# GPS.net
KiCad netlist of a schematic drawn in Altium Designer
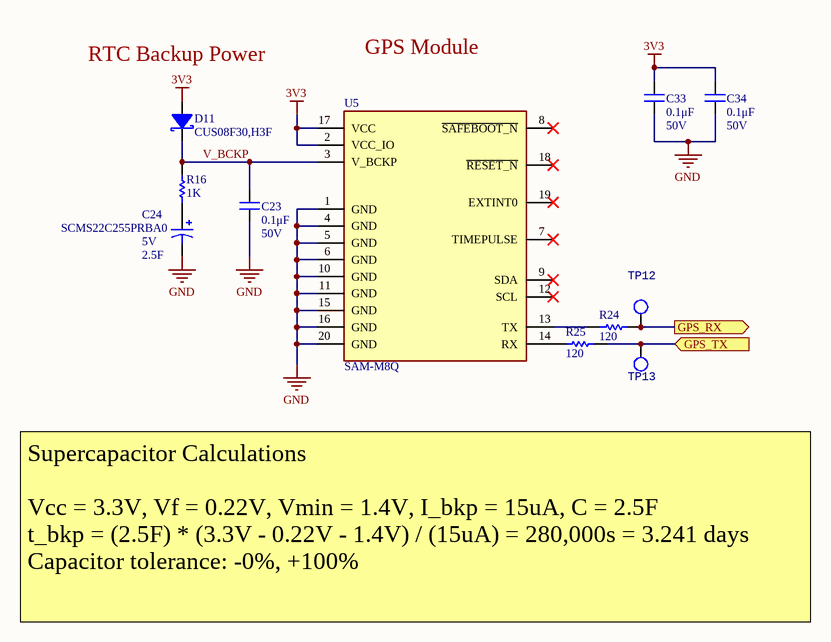
[diagram p0: GPS.SchDoc]

(export (version "E")
  (design (tool "Eeschema 10.0.6"))
  (components
    (comp (ref "C23")
      (value "0.1μF")
      (footprint "CAP2012")
      (description "CAP CER 0.1UF 50V X7R 0805")
      (fields
        (field (name "TOLERANCE") "10%")
        (field (name "VOLTAGE RATING") "50V")
        (field (name "Comment") "CAP_0.1uF_50V_0805")
      )
      (libsource (lib "UWRT_Schematic_Library_2020") (part "CAP_0.1uF_50V_0805"))
    )
    (comp (ref "C24")
      (value "CAP_2.5F_5V")
      (footprint "UWRT_Footprint_Library_2020:SCMS22C255PRBA0")
      (description "CAP 2.5F 5V")
      (fields
        (field (name "MANUFACTURER PART NUMBER 1") "SCMS22C255PRBA0")
        (field (name "TOLERANCE") "0%, +100%")
        (field (name "VOLTAGE RATING") "5V")
        (field (name "CAPACITANCE") "2.5F")
      )
      (libsource (lib "UWRT_Schematic_Library_2020") (part "CAP_2.5F_5V"))
    )
    (comp (ref "C33")
      (value "0.1μF")
      (footprint "CAP2012")
      (description "CAP CER 0.1UF 50V X7R 0805")
      (fields
        (field (name "TOLERANCE") "10%")
        (field (name "VOLTAGE RATING") "50V")
        (field (name "Comment") "CAP_0.1uF_50V_0805")
      )
      (libsource (lib "UWRT_Schematic_Library_2020") (part "CAP_0.1uF_50V_0805"))
    )
    (comp (ref "C34")
      (value "0.1μF")
      (footprint "CAP2012")
      (description "CAP CER 0.1UF 50V X7R 0805")
      (fields
        (field (name "TOLERANCE") "10%")
        (field (name "VOLTAGE RATING") "50V")
        (field (name "Comment") "CAP_0.1uF_50V_0805")
      )
      (libsource (lib "UWRT_Schematic_Library_2020") (part "CAP_0.1uF_50V_0805"))
    )
    (comp (ref "D11")
      (value "DIO_SCHOTTKY_30V_800mA")
      (footprint "SOD-323_UNIDIR")
      (description "DIODE SCHOTTKY 30V 800MA USC")
      (fields (field (name "MANUFACTURER PART NUMBER 1") "CUS08F30,H3F"))
      (libsource (lib "UWRT_Schematic_Library_2020") (part "DIO_SCHOTTKY_30V_800mA"))
    )
    (comp (ref "R16")
      (value "1K")
      (footprint "RESC0603(1608)_N")
      (description "RES SMD 1K OHM 5% 1/10W 0603")
      (fields (field (name "TOLERANCE") "5%") (field (name "Comment") "RES_1K_0603"))
      (libsource (lib "UWRT_Schematic_Library_2020") (part "RES_1K_0603"))
    )
    (comp (ref "R24")
      (value "120")
      (footprint "RESC0603(1608)_N")
      (description "RES SMD 120 OHM 5% 1/10W 0603")
      (fields (field (name "TOLERANCE") "5%") (field (name "Comment") "RES_120R_0603"))
      (libsource (lib "UWRT_Schematic_Library_2020") (part "RES_120R_0603"))
    )
    (comp (ref "R25")
      (value "120")
      (footprint "RESC0603(1608)_N")
      (description "RES SMD 120 OHM 5% 1/10W 0603")
      (fields (field (name "TOLERANCE") "5%") (field (name "Comment") "RES_120R_0603"))
      (libsource (lib "UWRT_Schematic_Library_2020") (part "RES_120R_0603"))
    )
    (comp (ref "TP12")
      (value "TESTPOINT_LOOP")
      (footprint "TESTPOINT_LOOP")
      (description "PC TEST POINT MINIATURE WHITE")
      (libsource (lib "UWRT_Schematic_Library_2020") (part "TESTPOINT_LOOP"))
    )
    (comp (ref "TP13")
      (value "TESTPOINT_LOOP")
      (footprint "TESTPOINT_LOOP")
      (description "PC TEST POINT MINIATURE WHITE")
      (libsource (lib "UWRT_Schematic_Library_2020") (part "TESTPOINT_LOOP"))
    )
    (comp (ref "U5")
      (value "SAM-M8Q")
      (footprint "SAM-M8Q")
      (description "Rf Rx Galileo 1.575GHZ/1.602GHZ")
      (libsource (lib "UWRT_Schematic_Library_2020") (part "SAM-M8Q"))
    )
  )
  (nets
    (net (code "1") (name "/GPS_RX") (class "Default")
      (node (ref "R24") (pin "2") (pinfunction "2_2") (pintype "passive"))
      (node (ref "TP12") (pin "1") (pintype "passive"))
    )
    (net (code "2") (name "/GPS_TX") (class "Default")
      (node (ref "R25") (pin "2") (pinfunction "2_2") (pintype "passive"))
      (node (ref "TP13") (pin "1") (pintype "passive"))
    )
    (net (code "3") (name "/V_BCKP") (class "Default")
      (node (ref "C23") (pin "2") (pinfunction "2_2") (pintype "passive"))
      (node (ref "D11") (pin "2") (pinfunction "Cathode_2") (pintype "passive"))
      (node (ref "R16") (pin "1") (pinfunction "1_1") (pintype "passive"))
      (node (ref "U5") (pin "3") (pinfunction "V_BCKP_3") (pintype "power_in"))
    )
    (net (code "4") (name "3V3") (class "Default")
      (node (ref "C33") (pin "2") (pinfunction "2_2") (pintype "passive"))
      (node (ref "C34") (pin "2") (pinfunction "2_2") (pintype "passive"))
      (node (ref "D11") (pin "1") (pinfunction "Anode_1") (pintype "passive"))
      (node (ref "U5") (pin "17") (pinfunction "VCC_17") (pintype "power_in"))
      (node (ref "U5") (pin "2") (pinfunction "VCC_IO_2") (pintype "power_in"))
    )
    (net (code "5") (name "GND") (class "Default")
      (node (ref "C23") (pin "1") (pinfunction "1_1") (pintype "passive"))
      (node (ref "C24") (pin "2") (pinfunction "2_2") (pintype "passive"))
      (node (ref "C33") (pin "1") (pinfunction "1_1") (pintype "passive"))
      (node (ref "C34") (pin "1") (pinfunction "1_1") (pintype "passive"))
      (node (ref "U5") (pin "1") (pinfunction "GND_1") (pintype "power_in"))
      (node (ref "U5") (pin "10") (pinfunction "GND_10") (pintype "power_in"))
      (node (ref "U5") (pin "11") (pinfunction "GND_11") (pintype "power_in"))
      (node (ref "U5") (pin "15") (pinfunction "GND_15") (pintype "power_in"))
      (node (ref "U5") (pin "16") (pinfunction "GND_16") (pintype "power_in"))
      (node (ref "U5") (pin "20") (pinfunction "GND_20") (pintype "power_in"))
      (node (ref "U5") (pin "4") (pinfunction "GND_4") (pintype "power_in"))
      (node (ref "U5") (pin "5") (pinfunction "GND_5") (pintype "power_in"))
      (node (ref "U5") (pin "6") (pinfunction "GND_6") (pintype "power_in"))
    )
    (net (code "6") (name "Net-(C24-Pad1)") (class "Default")
      (node (ref "C24") (pin "1") (pinfunction "1_1") (pintype "passive"))
      (node (ref "R16") (pin "2") (pinfunction "2_2") (pintype "passive"))
    )
    (net (code "7") (name "Net-(U5-RX)") (class "Default")
      (node (ref "R25") (pin "1") (pinfunction "1_1") (pintype "passive"))
      (node (ref "U5") (pin "14") (pinfunction "RX_14") (pintype "passive"))
    )
    (net (code "8") (name "Net-(U5-TX)") (class "Default")
      (node (ref "R24") (pin "1") (pinfunction "1_1") (pintype "passive"))
      (node (ref "U5") (pin "13") (pinfunction "TX_13") (pintype "passive"))
    )
    (net (code "9") (name "unconnected-(U5-EXTINT0-Pad19)") (class "Default")
      (node (ref "U5") (pin "19") (pinfunction "EXTINT0_19") (pintype "passive+no_connect"))
    )
    (net (code "10") (name "unconnected-(U5-SCL-Pad12)") (class "Default")
      (node (ref "U5") (pin "12") (pinfunction "SCL_12") (pintype "passive+no_connect"))
    )
    (net (code "11") (name "unconnected-(U5-SDA-Pad9)") (class "Default")
      (node (ref "U5") (pin "9") (pinfunction "SDA_9") (pintype "passive+no_connect"))
    )
    (net (code "12") (name "unconnected-(U5-TIMEPULSE-Pad7)") (class "Default")
      (node (ref "U5") (pin "7") (pinfunction "TIMEPULSE_7") (pintype "passive+no_connect"))
    )
    (net (code "13") (name "unconnected-(U5-~{RESET_N}-Pad18)") (class "Default")
      (node (ref "U5") (pin "18") (pinfunction "~{RESET_N}_18") (pintype "passive+no_connect"))
    )
    (net (code "14") (name "unconnected-(U5-~{SAFEBOOT_N}-Pad8)") (class "Default")
      (node (ref "U5") (pin "8") (pinfunction "~{SAFEBOOT_N}_8") (pintype "passive+no_connect"))
    )
  )
)
